# RGB_LEDs.net
KiCad netlist of a schematic drawn in Altium Designer
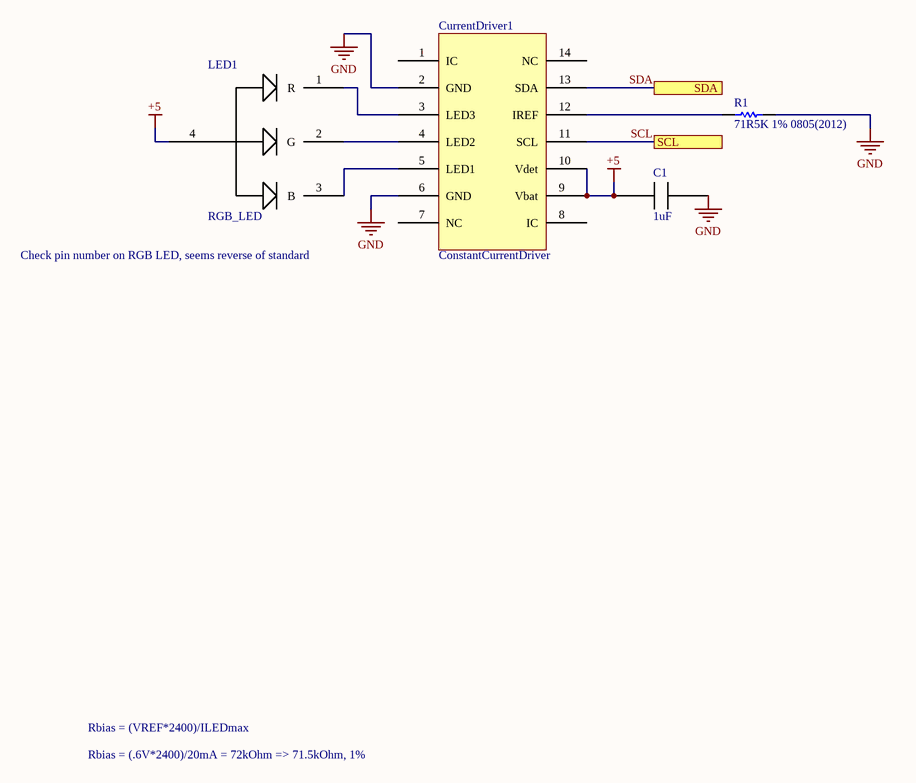
[diagram p0: RGB_LEDs.SchDoc]

(export (version "E")
  (design (tool "Eeschema 10.0.6"))
  (components
    (comp (ref "C1") (value "1uF") (footprint "0805") (libsource (lib "PSoC Devboard CAN Cape") (part "Cap")))
    (comp (ref "CurrentDriver1")
      (value "ConstantCurrentDriver")
      (footprint "NCP5623")
      (libsource (lib "PSoC Devboard CAN Cape") (part "ConstantCurrentDriver"))
    )
    (comp (ref "LED1")
      (value "RGB_LED")
      (footprint "ASMB-MTB1-0A3A2")
      (libsource (lib "PSoC Devboard CAN Cape") (part "RGB_LED"))
    )
    (comp (ref "R1")
      (value "71R5K 1% 0805(2012)")
      (footprint "RESC0805(2012)_N")
      (description "120R 0.125W 5% 0805 (2012 Metric)  SMD")
      (fields (field (name "TOLERANCE") "5 %") (field (name "POWER") "0.125 W"))
      (libsource (lib "Husky Robotics Standard Library 2019-2020") (part "120R 5% 0805"))
    )
  )
  (nets
    (net (code "1") (name "+5") (class "Default")
      (node (ref "C1") (pin "1") (pinfunction "1_1") (pintype "passive"))
      (node (ref "CurrentDriver1") (pin "10") (pinfunction "Vdet_10") (pintype "passive"))
      (node (ref "CurrentDriver1") (pin "9") (pinfunction "Vbat_9") (pintype "passive"))
      (node (ref "LED1") (pin "4") (pinfunction "4_4") (pintype "passive"))
    )
    (net (code "2") (name "/SCL") (class "Default")
      (node (ref "CurrentDriver1") (pin "11") (pinfunction "SCL_11") (pintype "passive"))
    )
    (net (code "3") (name "/SDA") (class "Default")
      (node (ref "CurrentDriver1") (pin "13") (pinfunction "SDA_13") (pintype "passive"))
    )
    (net (code "4") (name "GND") (class "Default")
      (node (ref "C1") (pin "2") (pinfunction "2_2") (pintype "passive"))
      (node (ref "CurrentDriver1") (pin "2") (pinfunction "GND_2") (pintype "passive"))
      (node (ref "CurrentDriver1") (pin "6") (pinfunction "GND_6") (pintype "passive"))
      (node (ref "R1") (pin "2") (pinfunction "2_2") (pintype "passive"))
    )
    (net (code "5") (name "Net-(CurrentDriver1-IREF)") (class "Default")
      (node (ref "CurrentDriver1") (pin "12") (pinfunction "IREF_12") (pintype "passive"))
      (node (ref "R1") (pin "1") (pinfunction "1_1") (pintype "passive"))
    )
    (net (code "6") (name "Net-(CurrentDriver1-LED1)") (class "Default")
      (node (ref "CurrentDriver1") (pin "5") (pinfunction "LED1_5") (pintype "passive"))
      (node (ref "LED1") (pin "3") (pinfunction "B_3") (pintype "passive"))
    )
    (net (code "7") (name "Net-(CurrentDriver1-LED2)") (class "Default")
      (node (ref "CurrentDriver1") (pin "4") (pinfunction "LED2_4") (pintype "passive"))
      (node (ref "LED1") (pin "2") (pinfunction "G_2") (pintype "passive"))
    )
    (net (code "8") (name "Net-(CurrentDriver1-LED3)") (class "Default")
      (node (ref "CurrentDriver1") (pin "3") (pinfunction "LED3_3") (pintype "passive"))
      (node (ref "LED1") (pin "1") (pinfunction "R_1") (pintype "passive"))
    )
    (net (code "9") (name "unconnected-(CurrentDriver1-IC-Pad1)") (class "Default")
      (node (ref "CurrentDriver1") (pin "1") (pinfunction "IC_1") (pintype "passive"))
    )
    (net (code "10") (name "unconnected-(CurrentDriver1-IC-Pad8)") (class "Default")
      (node (ref "CurrentDriver1") (pin "8") (pinfunction "IC_8") (pintype "passive"))
    )
    (net (code "11") (name "unconnected-(CurrentDriver1-NC-Pad7)") (class "Default")
      (node (ref "CurrentDriver1") (pin "7") (pinfunction "NC_7") (pintype "passive"))
    )
    (net (code "12") (name "unconnected-(CurrentDriver1-NC-Pad14)") (class "Default")
      (node (ref "CurrentDriver1") (pin "14") (pinfunction "NC_14") (pintype "passive"))
    )
  )
)
